# M597D.net
KiCad netlist of a schematic drawn in EAGLE
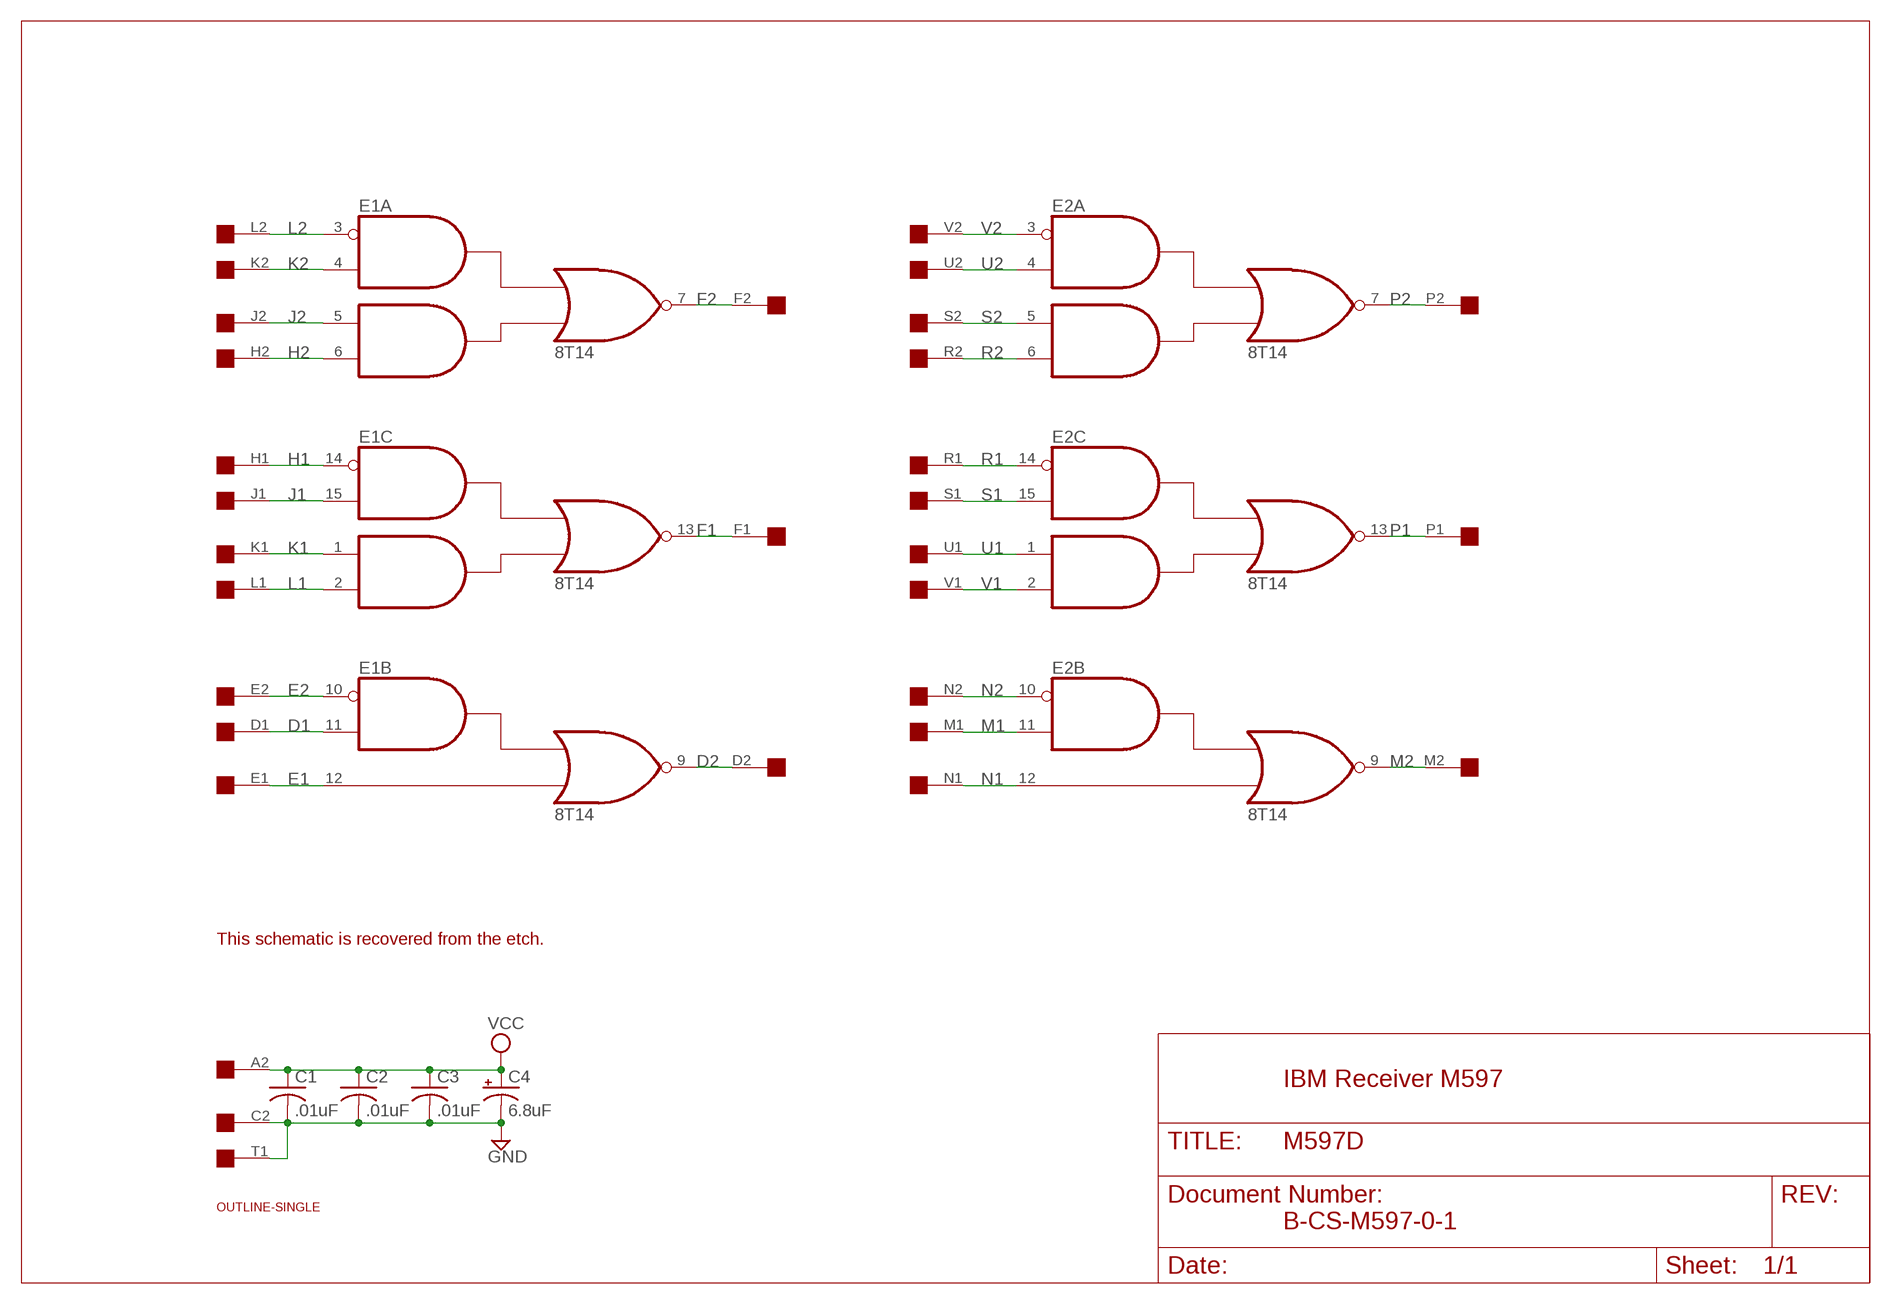
[diagram p0: schematic, sheet 1]

(export (version "E")
  (design (tool "Eeschema 10.0.6"))
  (components
    (comp (ref "C1")
      (value ".01uF")
      (footprint "eagle-import:C050-025X075")
      (libsource (lib "eagle-import") (part "C-US050-025X075"))
    )
    (comp (ref "C2")
      (value ".01uF")
      (footprint "eagle-import:C050-025X075")
      (libsource (lib "eagle-import") (part "C-US050-025X075"))
    )
    (comp (ref "C3")
      (value ".01uF")
      (footprint "eagle-import:C050-025X075")
      (libsource (lib "eagle-import") (part "C-US050-025X075"))
    )
    (comp (ref "C4")
      (value "6.8uF")
      (footprint "eagle-import:E12-8")
      (libsource (lib "eagle-import") (part "CPOL-USE20-8AXIAL"))
    )
    (comp (ref "E1")
      (value "8T14")
      (footprint "eagle-import:DIL16")
      (libsource (lib "eagle-import") (part "8T14"))
    )
    (comp (ref "E2")
      (value "8T14")
      (footprint "eagle-import:DIL16")
      (libsource (lib "eagle-import") (part "8T14"))
    )
    (comp (ref "U$2")
      (value "SINGLE")
      (footprint "eagle-import:EDGE-CON2")
      (libsource (lib "eagle-import") (part "SINGLE"))
    )
    (comp (ref "U$4")
      (value "OUTLINE-SINGLE")
      (footprint "eagle-import:SINGLE")
      (libsource (lib "eagle-import") (part "OUTLINE-SINGLE"))
    )
  )
  (nets
    (net (code "1") (name "/D1") (class "Default")
      (node (ref "E1") (pin "11") (pinfunction "S_11") (pintype "input"))
      (node (ref "U$2") (pin "D1") (pinfunction "1_D1") (pintype "bidirectional"))
    )
    (net (code "2") (name "/D2") (class "Default")
      (node (ref "E1") (pin "9") (pinfunction "O_9") (pintype "output"))
      (node (ref "U$2") (pin "D2") (pinfunction "1_D2") (pintype "bidirectional"))
    )
    (net (code "3") (name "/E1") (class "Default")
      (node (ref "E1") (pin "12") (pinfunction "I1_12") (pintype "input"))
      (node (ref "U$2") (pin "E1") (pinfunction "1_E1") (pintype "bidirectional"))
    )
    (net (code "4") (name "/E2") (class "Default")
      (node (ref "E1") (pin "10") (pinfunction "R_10") (pintype "input"))
      (node (ref "U$2") (pin "E2") (pinfunction "1_E2") (pintype "bidirectional"))
    )
    (net (code "5") (name "/F1") (class "Default")
      (node (ref "E1") (pin "13") (pinfunction "O_13") (pintype "output"))
      (node (ref "U$2") (pin "F1") (pinfunction "1_F1") (pintype "bidirectional"))
    )
    (net (code "6") (name "/F2") (class "Default")
      (node (ref "E1") (pin "7") (pinfunction "O_7") (pintype "output"))
      (node (ref "U$2") (pin "F2") (pinfunction "1_F2") (pintype "bidirectional"))
    )
    (net (code "7") (name "/H1") (class "Default")
      (node (ref "E1") (pin "14") (pinfunction "R_14") (pintype "input"))
      (node (ref "U$2") (pin "H1") (pinfunction "1_H1") (pintype "bidirectional"))
    )
    (net (code "8") (name "/H2") (class "Default")
      (node (ref "E1") (pin "6") (pinfunction "I2_6") (pintype "input"))
      (node (ref "U$2") (pin "H2") (pinfunction "1_H2") (pintype "bidirectional"))
    )
    (net (code "9") (name "/J1") (class "Default")
      (node (ref "E1") (pin "15") (pinfunction "S_15") (pintype "input"))
      (node (ref "U$2") (pin "J1") (pinfunction "1_J1") (pintype "bidirectional"))
    )
    (net (code "10") (name "/J2") (class "Default")
      (node (ref "E1") (pin "5") (pinfunction "I1_5") (pintype "input"))
      (node (ref "U$2") (pin "J2") (pinfunction "1_J2") (pintype "bidirectional"))
    )
    (net (code "11") (name "/K1") (class "Default")
      (node (ref "E1") (pin "1") (pinfunction "I1_1") (pintype "input"))
      (node (ref "U$2") (pin "K1") (pinfunction "1_K1") (pintype "bidirectional"))
    )
    (net (code "12") (name "/K2") (class "Default")
      (node (ref "E1") (pin "4") (pinfunction "S_4") (pintype "input"))
      (node (ref "U$2") (pin "K2") (pinfunction "1_K2") (pintype "bidirectional"))
    )
    (net (code "13") (name "/L1") (class "Default")
      (node (ref "E1") (pin "2") (pinfunction "I2_2") (pintype "input"))
      (node (ref "U$2") (pin "L1") (pinfunction "1_L1") (pintype "bidirectional"))
    )
    (net (code "14") (name "/L2") (class "Default")
      (node (ref "E1") (pin "3") (pinfunction "R_3") (pintype "input"))
      (node (ref "U$2") (pin "L2") (pinfunction "1_L2") (pintype "bidirectional"))
    )
    (net (code "15") (name "/M1") (class "Default")
      (node (ref "E2") (pin "11") (pinfunction "S_11") (pintype "input"))
      (node (ref "U$2") (pin "M1") (pinfunction "1_M1") (pintype "bidirectional"))
    )
    (net (code "16") (name "/M2") (class "Default")
      (node (ref "E2") (pin "9") (pinfunction "O_9") (pintype "output"))
      (node (ref "U$2") (pin "M2") (pinfunction "1_M2") (pintype "bidirectional"))
    )
    (net (code "17") (name "/N1") (class "Default")
      (node (ref "E2") (pin "12") (pinfunction "I1_12") (pintype "input"))
      (node (ref "U$2") (pin "N1") (pinfunction "1_N1") (pintype "bidirectional"))
    )
    (net (code "18") (name "/N2") (class "Default")
      (node (ref "E2") (pin "10") (pinfunction "R_10") (pintype "input"))
      (node (ref "U$2") (pin "N2") (pinfunction "1_N2") (pintype "bidirectional"))
    )
    (net (code "19") (name "/P1") (class "Default")
      (node (ref "E2") (pin "13") (pinfunction "O_13") (pintype "output"))
      (node (ref "U$2") (pin "P1") (pinfunction "1_P1") (pintype "bidirectional"))
    )
    (net (code "20") (name "/P2") (class "Default")
      (node (ref "E2") (pin "7") (pinfunction "O_7") (pintype "output"))
      (node (ref "U$2") (pin "P2") (pinfunction "1_P2") (pintype "bidirectional"))
    )
    (net (code "21") (name "/R1") (class "Default")
      (node (ref "E2") (pin "14") (pinfunction "R_14") (pintype "input"))
      (node (ref "U$2") (pin "R1") (pinfunction "1_R1") (pintype "bidirectional"))
    )
    (net (code "22") (name "/R2") (class "Default")
      (node (ref "E2") (pin "6") (pinfunction "I2_6") (pintype "input"))
      (node (ref "U$2") (pin "R2") (pinfunction "1_R2") (pintype "bidirectional"))
    )
    (net (code "23") (name "/S1") (class "Default")
      (node (ref "E2") (pin "15") (pinfunction "S_15") (pintype "input"))
      (node (ref "U$2") (pin "S1") (pinfunction "1_S1") (pintype "bidirectional"))
    )
    (net (code "24") (name "/S2") (class "Default")
      (node (ref "E2") (pin "5") (pinfunction "I1_5") (pintype "input"))
      (node (ref "U$2") (pin "S2") (pinfunction "1_S2") (pintype "bidirectional"))
    )
    (net (code "25") (name "/U1") (class "Default")
      (node (ref "E2") (pin "1") (pinfunction "I1_1") (pintype "input"))
      (node (ref "U$2") (pin "U1") (pinfunction "1_U1") (pintype "bidirectional"))
    )
    (net (code "26") (name "/U2") (class "Default")
      (node (ref "E2") (pin "4") (pinfunction "S_4") (pintype "input"))
      (node (ref "U$2") (pin "U2") (pinfunction "1_U2") (pintype "bidirectional"))
    )
    (net (code "27") (name "/V1") (class "Default")
      (node (ref "E2") (pin "2") (pinfunction "I2_2") (pintype "input"))
      (node (ref "U$2") (pin "V1") (pinfunction "1_V1") (pintype "bidirectional"))
    )
    (net (code "28") (name "/V2") (class "Default")
      (node (ref "E2") (pin "3") (pinfunction "R_3") (pintype "input"))
      (node (ref "U$2") (pin "V2") (pinfunction "1_V2") (pintype "bidirectional"))
    )
    (net (code "29") (name "GND") (class "Default")
      (node (ref "C1") (pin "2") (pinfunction "2_2") (pintype "passive"))
      (node (ref "C2") (pin "2") (pinfunction "2_2") (pintype "passive"))
      (node (ref "C3") (pin "2") (pinfunction "2_2") (pintype "passive"))
      (node (ref "C4") (pin "-") (pinfunction "-_-") (pintype "passive"))
      (node (ref "U$2") (pin "C2") (pinfunction "1_C2") (pintype "bidirectional"))
      (node (ref "U$2") (pin "T1") (pinfunction "1_T1") (pintype "bidirectional"))
    )
    (net (code "30") (name "VCC") (class "Default")
      (node (ref "C1") (pin "1") (pinfunction "1_1") (pintype "passive"))
      (node (ref "C2") (pin "1") (pinfunction "1_1") (pintype "passive"))
      (node (ref "C3") (pin "1") (pinfunction "1_1") (pintype "passive"))
      (node (ref "C4") (pin "+") (pinfunction "+_+") (pintype "passive"))
      (node (ref "U$2") (pin "A2") (pinfunction "1_A2") (pintype "bidirectional"))
    )
  )
)
